# VoltageMonitor.net
KiCad netlist of a schematic drawn in Altium Designer
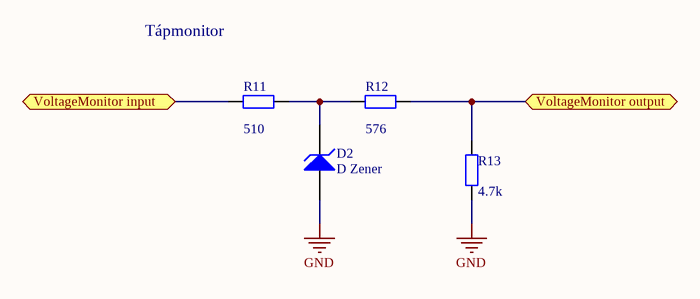
[diagram p0: VoltageMonitor.SchDoc]

(export (version "E")
  (design (tool "Eeschema 10.0.6"))
  (components
    (comp (ref "D2")
      (value "D Zener")
      (footprint "AXIAL-0.4")
      (description "Zener Diode")
      (fields (field (name "PUBLISHER") "Altium Limited"))
      (libsource (lib "Miscellaneous Devices") (part "D Zener"))
    )
    (comp (ref "R11")
      (value "510")
      (footprint "AXIAL-0.4")
      (description "Resistor")
      (fields (field (name "Comment") "500") (field (name "PUBLISHER") "Altium Limited"))
      (libsource (lib "Miscellaneous Devices") (part "Res2"))
    )
    (comp (ref "R12")
      (value "576")
      (footprint "AXIAL-0.4")
      (description "Resistor")
      (fields (field (name "PUBLISHER") "Altium Limited"))
      (libsource (lib "Miscellaneous Devices") (part "Res2"))
    )
    (comp (ref "R13")
      (value "4.7k")
      (footprint "AXIAL-0.4")
      (description "Resistor")
      (fields (field (name "PUBLISHER") "Altium Limited"))
      (libsource (lib "") (part "Res2_1"))
    )
  )
  (nets
    (net (code "1") (name "/VoltageMonitor input") (class "Default")
      (node (ref "R11") (pin "2") (pinfunction "2_2") (pintype "passive"))
    )
    (net (code "2") (name "/VoltageMonitor output") (class "Default")
      (node (ref "R12") (pin "1") (pinfunction "1_1") (pintype "passive"))
      (node (ref "R13") (pin "1") (pinfunction "1_1") (pintype "passive"))
    )
    (net (code "3") (name "GND") (class "Default")
      (node (ref "D2") (pin "1") (pinfunction "A_1") (pintype "passive"))
      (node (ref "R13") (pin "2") (pinfunction "2_2") (pintype "passive"))
    )
    (net (code "4") (name "Net-(D2-K)") (class "Default")
      (node (ref "D2") (pin "2") (pinfunction "K_2") (pintype "passive"))
      (node (ref "R11") (pin "1") (pinfunction "1_1") (pintype "passive"))
      (node (ref "R12") (pin "2") (pinfunction "2_2") (pintype "passive"))
    )
  )
)
